# pm2013.net
KiCad netlist of a schematic drawn in EAGLE
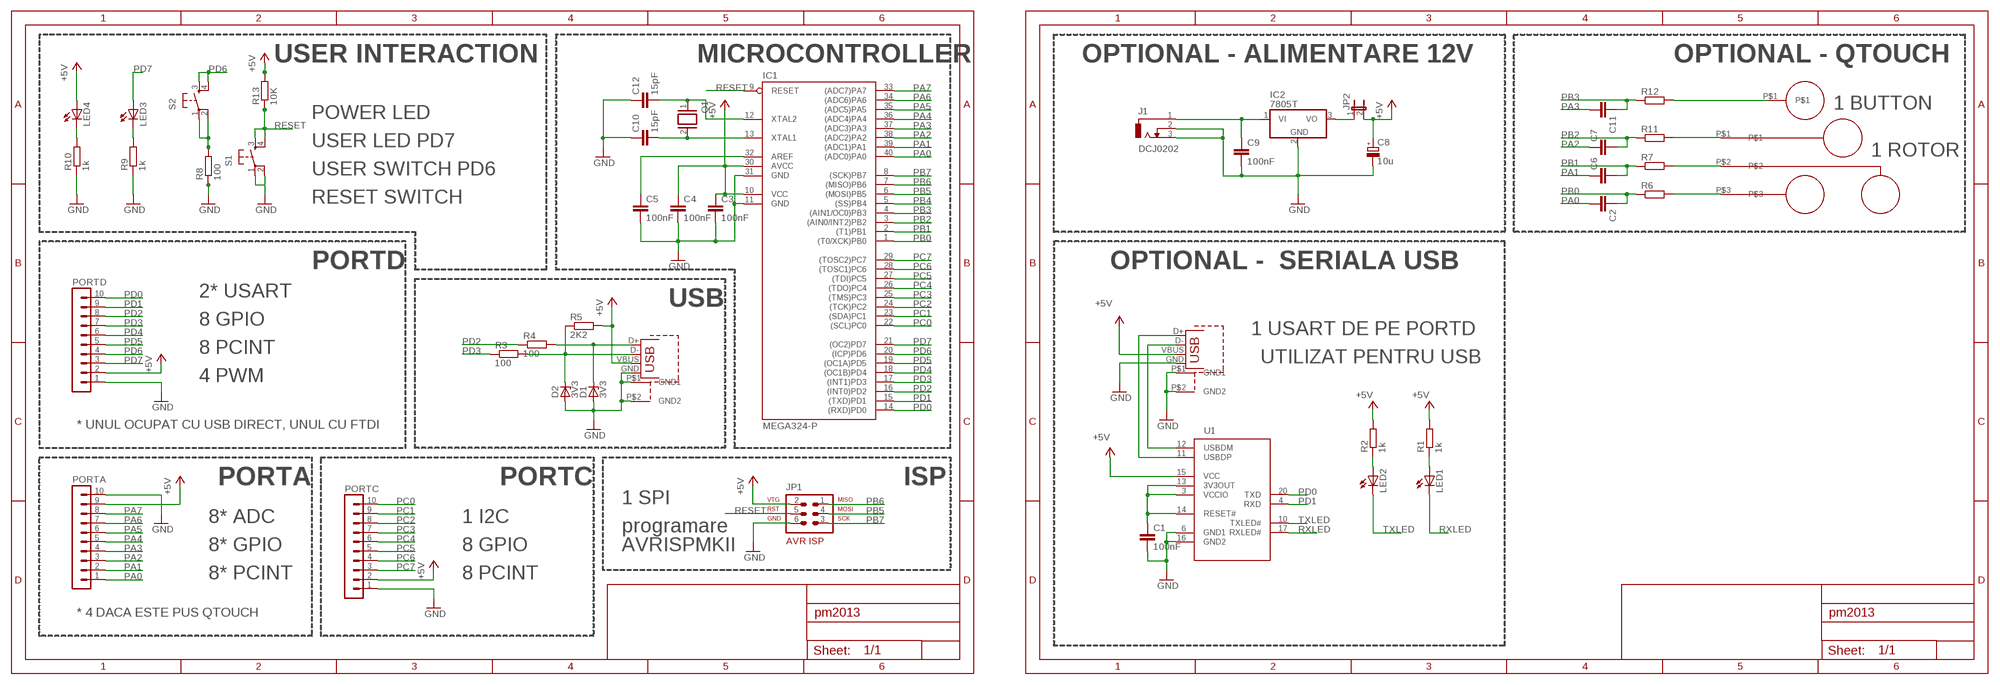
[diagram p0: schematic, sheet 1]

(export (version "E")
  (design (tool "Eeschema 10.0.6"))
  (components
    (comp (ref "C1")
      (value "100nF")
      (footprint "eagle-import:C025-025X050")
      (libsource (lib "eagle-import") (part "C-EU025-025X050"))
    )
    (comp (ref "C2")
      (value "C-EUC1206")
      (footprint "eagle-import:C1206")
      (libsource (lib "eagle-import") (part "C-EUC1206"))
    )
    (comp (ref "C3")
      (value "100nF")
      (footprint "eagle-import:C025-025X050")
      (libsource (lib "eagle-import") (part "C-EU025-025X050"))
    )
    (comp (ref "C4")
      (value "100nF")
      (footprint "eagle-import:C025-025X050")
      (libsource (lib "eagle-import") (part "C-EU025-025X050"))
    )
    (comp (ref "C5")
      (value "100nF")
      (footprint "eagle-import:C025-025X050")
      (libsource (lib "eagle-import") (part "C-EU025-025X050"))
    )
    (comp (ref "C6")
      (value "C-EUC1206")
      (footprint "eagle-import:C1206")
      (libsource (lib "eagle-import") (part "C-EUC1206"))
    )
    (comp (ref "C7")
      (value "C-EUC1206")
      (footprint "eagle-import:C1206")
      (libsource (lib "eagle-import") (part "C-EUC1206"))
    )
    (comp (ref "C8")
      (value "10u")
      (footprint "eagle-import:E2,5-5")
      (libsource (lib "eagle-import") (part "CPOL-EUE2.5-5"))
    )
    (comp (ref "C9")
      (value "100nF")
      (footprint "eagle-import:C025-025X050")
      (libsource (lib "eagle-import") (part "C-EU025-025X050"))
    )
    (comp (ref "C10")
      (value "15pF")
      (footprint "eagle-import:C025-025X050")
      (libsource (lib "eagle-import") (part "C-EU025-025X050"))
    )
    (comp (ref "C11")
      (value "C-EUC1206")
      (footprint "eagle-import:C1206")
      (libsource (lib "eagle-import") (part "C-EUC1206"))
    )
    (comp (ref "C12")
      (value "15pF")
      (footprint "eagle-import:C025-025X050")
      (libsource (lib "eagle-import") (part "C-EU025-025X050"))
    )
    (comp (ref "D1")
      (value "3V3")
      (footprint "eagle-import:DO34Z7")
      (libsource (lib "eagle-import") (part "ZENER-DIODEDO34-7"))
    )
    (comp (ref "D2")
      (value "3V3")
      (footprint "eagle-import:DO34Z7")
      (libsource (lib "eagle-import") (part "ZENER-DIODEDO34-7"))
    )
    (comp (ref "IC1")
      (value "MEGA324-P")
      (footprint "eagle-import:DIL40")
      (fields (field (name "MPN") "ATMEGA16-16PU"))
      (libsource (lib "eagle-import") (part "MEGA16-P"))
    )
    (comp (ref "IC2")
      (value "7805T")
      (footprint "eagle-import:TO220H")
      (libsource (lib "eagle-import") (part "78T05"))
    )
    (comp (ref "J1")
      (value "DCJ0202")
      (footprint "eagle-import:DCJ0202")
      (libsource (lib "eagle-import") (part "DCJ0202"))
    )
    (comp (ref "JP1")
      (value "AVR-ISP-6")
      (footprint "eagle-import:AVR-ISP-6")
      (libsource (lib "eagle-import") (part "AVR-ISP-6"))
    )
    (comp (ref "JP2")
      (value "JP1E")
      (footprint "eagle-import:JP1")
      (libsource (lib "eagle-import") (part "JP1E"))
    )
    (comp (ref "LED1")
      (value "TLLR4400")
      (footprint "eagle-import:LED3MM")
      (fields
        (field (name "MF") "VISHAY SEMICONDUCTOR")
        (field (name "MF_1") "VISHAY SEMICONDUCTOR")
        (field (name "OC_FARNELL") "1612437")
      )
      (libsource (lib "eagle-import") (part "TLLR4400"))
    )
    (comp (ref "LED2")
      (value "TLLR4400")
      (footprint "eagle-import:LED3MM")
      (fields
        (field (name "MF") "VISHAY SEMICONDUCTOR")
        (field (name "MF_1") "VISHAY SEMICONDUCTOR")
        (field (name "OC_FARNELL") "1612437")
      )
      (libsource (lib "eagle-import") (part "TLLR4400"))
    )
    (comp (ref "LED3")
      (value "TLLR4400")
      (footprint "eagle-import:LED3MM")
      (fields (field (name "MF") "VISHAY SEMICONDUCTOR"))
      (libsource (lib "eagle-import") (part "TLLR4400"))
    )
    (comp (ref "LED4")
      (value "TLLR4400")
      (footprint "eagle-import:LED3MM")
      (fields (field (name "MF") "VISHAY SEMICONDUCTOR"))
      (libsource (lib "eagle-import") (part "TLLR4400"))
    )
    (comp (ref "PORTA")
      (value "MA10-1W")
      (footprint "eagle-import:MA10-1W")
      (libsource (lib "eagle-import") (part "MA10-1W"))
    )
    (comp (ref "PORTC")
      (value "MA10-1W")
      (footprint "eagle-import:MA10-1W")
      (libsource (lib "eagle-import") (part "MA10-1W"))
    )
    (comp (ref "PORTD")
      (value "MA10-1W")
      (footprint "eagle-import:MA10-1W")
      (libsource (lib "eagle-import") (part "MA10-1W"))
    )
    (comp (ref "Q1")
      (value "XTAL/S")
      (footprint "eagle-import:QS")
      (libsource (lib "eagle-import") (part "XTAL/S"))
    )
    (comp (ref "R1")
      (value "1k")
      (footprint "eagle-import:0204_7")
      (libsource (lib "eagle-import") (part "R-EU_0204/7"))
    )
    (comp (ref "R2")
      (value "1k")
      (footprint "eagle-import:0204_7")
      (libsource (lib "eagle-import") (part "R-EU_0204/7"))
    )
    (comp (ref "R3")
      (value "100")
      (footprint "eagle-import:0204_7")
      (libsource (lib "eagle-import") (part "R-EU_0204/7"))
    )
    (comp (ref "R4")
      (value "100")
      (footprint "eagle-import:0204_7")
      (libsource (lib "eagle-import") (part "R-EU_0204/7"))
    )
    (comp (ref "R5")
      (value "2K2")
      (footprint "eagle-import:0204_7")
      (libsource (lib "eagle-import") (part "R-EU_0204/7"))
    )
    (comp (ref "R6")
      (value "R-EU_M1206")
      (footprint "eagle-import:M1206")
      (libsource (lib "eagle-import") (part "resistor_R-EU_M1206"))
    )
    (comp (ref "R7")
      (value "R-EU_M1206")
      (footprint "eagle-import:M1206")
      (libsource (lib "eagle-import") (part "resistor_R-EU_M1206"))
    )
    (comp (ref "R8")
      (value "100")
      (footprint "eagle-import:0204_7")
      (libsource (lib "eagle-import") (part "R-EU_0204/7"))
    )
    (comp (ref "R9")
      (value "1k")
      (footprint "eagle-import:0204_7")
      (libsource (lib "eagle-import") (part "resistor_R-EU_0204/7"))
    )
    (comp (ref "R10")
      (value "1k")
      (footprint "eagle-import:0204_7")
      (libsource (lib "eagle-import") (part "resistor_R-EU_0204/7"))
    )
    (comp (ref "R11")
      (value "R-EU_M1206")
      (footprint "eagle-import:M1206")
      (libsource (lib "eagle-import") (part "resistor_R-EU_M1206"))
    )
    (comp (ref "R12")
      (value "R-EU_M1206")
      (footprint "eagle-import:M1206")
      (libsource (lib "eagle-import") (part "resistor_R-EU_M1206"))
    )
    (comp (ref "R13")
      (value "10K")
      (footprint "eagle-import:0204_7")
      (libsource (lib "eagle-import") (part "R-EU_0204/7"))
    )
    (comp (ref "S1")
      (value "TAC_SWITCHPTH")
      (footprint "eagle-import:TACTILE-PTH")
      (libsource (lib "eagle-import") (part "TAC_SWITCHPTH"))
    )
    (comp (ref "S2")
      (value "TAC_SWITCHPTH")
      (footprint "eagle-import:TACTILE-PTH")
      (libsource (lib "eagle-import") (part "TAC_SWITCHPTH"))
    )
    (comp (ref "U$1")
      (value "ROTOR_ELECTRODE_TOUCH")
      (footprint "eagle-import:ROTOR_ELECTRODE_TOUCH")
      (libsource (lib "eagle-import") (part "ROTOR_ELECTRODE_TOUCH"))
    )
    (comp (ref "U$2")
      (value "SIMPLE_ELECTRODE_TOUCH")
      (footprint "eagle-import:SIMPLE_ELECTRODE_TOUCH")
      (libsource (lib "eagle-import") (part "SIMPLE_ELECTRODE_TOUCH"))
    )
    (comp (ref "U1")
      (value "FT231XS")
      (footprint "eagle-import:SSOP20")
      (libsource (lib "eagle-import") (part "FT231XS"))
    )
    (comp (ref "X1")
      (value "USB")
      (footprint "eagle-import:USB-B-PTH")
      (libsource (lib "eagle-import") (part "USB"))
    )
    (comp (ref "X2")
      (value "USBPTH")
      (footprint "eagle-import:USB-B-PTH")
      (libsource (lib "eagle-import") (part "USB"))
    )
  )
  (nets
    (net (code "1") (name "+5V") (class "Default")
      (node (ref "C3") (pin "1") (pinfunction "1_1") (pintype "passive"))
      (node (ref "C4") (pin "1") (pinfunction "1_1") (pintype "passive"))
      (node (ref "C8") (pin "+") (pinfunction "+_+") (pintype "passive"))
      (node (ref "IC1") (pin "10") (pinfunction "VCC_10") (pintype "power_in"))
      (node (ref "IC1") (pin "30") (pinfunction "AVCC_30") (pintype "power_in"))
      (node (ref "JP1") (pin "2") (pinfunction "2_2") (pintype "passive"))
      (node (ref "JP2") (pin "2") (pinfunction "2_2") (pintype "passive"))
      (node (ref "LED4") (pin "A") (pinfunction "A_A") (pintype "passive"))
      (node (ref "PORTA") (pin "9") (pinfunction "9_9") (pintype "passive"))
      (node (ref "PORTC") (pin "2") (pinfunction "2_2") (pintype "passive"))
      (node (ref "PORTD") (pin "2") (pinfunction "2_2") (pintype "passive"))
      (node (ref "R1") (pin "2") (pinfunction "2_2") (pintype "passive"))
      (node (ref "R13") (pin "2") (pinfunction "2_2") (pintype "passive"))
      (node (ref "R2") (pin "2") (pinfunction "2_2") (pintype "passive"))
      (node (ref "R5") (pin "2") (pinfunction "2_2") (pintype "passive"))
      (node (ref "U1") (pin "15") (pinfunction "VCC_15") (pintype "power_in"))
      (node (ref "X1") (pin "VBUS") (pinfunction "VBUS_VBUS") (pintype "bidirectional"))
      (node (ref "X2") (pin "VBUS") (pinfunction "VBUS_VBUS") (pintype "bidirectional"))
    )
    (net (code "2") (name "/PA0") (class "Default")
      (node (ref "C2") (pin "2") (pinfunction "2_2") (pintype "passive"))
      (node (ref "IC1") (pin "40") (pinfunction "(ADC0)PA0_40") (pintype "bidirectional"))
      (node (ref "PORTA") (pin "1") (pinfunction "1_1") (pintype "passive"))
    )
    (net (code "3") (name "/PA1") (class "Default")
      (node (ref "C6") (pin "1") (pinfunction "1_1") (pintype "passive"))
      (node (ref "IC1") (pin "39") (pinfunction "(ADC1)PA1_39") (pintype "bidirectional"))
      (node (ref "PORTA") (pin "2") (pinfunction "2_2") (pintype "passive"))
    )
    (net (code "4") (name "/PA2") (class "Default")
      (node (ref "C7") (pin "1") (pinfunction "1_1") (pintype "passive"))
      (node (ref "IC1") (pin "38") (pinfunction "(ADC2)PA2_38") (pintype "bidirectional"))
      (node (ref "PORTA") (pin "3") (pinfunction "3_3") (pintype "passive"))
    )
    (net (code "5") (name "/PA3") (class "Default")
      (node (ref "C11") (pin "2") (pinfunction "2_2") (pintype "passive"))
      (node (ref "IC1") (pin "37") (pinfunction "(ADC3)PA3_37") (pintype "bidirectional"))
      (node (ref "PORTA") (pin "4") (pinfunction "4_4") (pintype "passive"))
    )
    (net (code "6") (name "/PA4") (class "Default")
      (node (ref "IC1") (pin "36") (pinfunction "(ADC4)PA4_36") (pintype "bidirectional"))
      (node (ref "PORTA") (pin "5") (pinfunction "5_5") (pintype "passive"))
    )
    (net (code "7") (name "/PA5") (class "Default")
      (node (ref "IC1") (pin "35") (pinfunction "(ADC5)PA5_35") (pintype "bidirectional"))
      (node (ref "PORTA") (pin "6") (pinfunction "6_6") (pintype "passive"))
    )
    (net (code "8") (name "/PA6") (class "Default")
      (node (ref "IC1") (pin "34") (pinfunction "(ADC6)PA6_34") (pintype "bidirectional"))
      (node (ref "PORTA") (pin "7") (pinfunction "7_7") (pintype "passive"))
    )
    (net (code "9") (name "/PA7") (class "Default")
      (node (ref "IC1") (pin "33") (pinfunction "(ADC7)PA7_33") (pintype "bidirectional"))
      (node (ref "PORTA") (pin "8") (pinfunction "8_8") (pintype "passive"))
    )
    (net (code "10") (name "/PB0") (class "Default")
      (node (ref "C2") (pin "1") (pinfunction "1_1") (pintype "passive"))
      (node (ref "IC1") (pin "1") (pinfunction "(T0/XCK)PB0_1") (pintype "bidirectional"))
      (node (ref "R6") (pin "1") (pinfunction "1_1") (pintype "passive"))
    )
    (net (code "11") (name "/PB1") (class "Default")
      (node (ref "C6") (pin "2") (pinfunction "2_2") (pintype "passive"))
      (node (ref "IC1") (pin "2") (pinfunction "(T1)PB1_2") (pintype "bidirectional"))
      (node (ref "R7") (pin "1") (pinfunction "1_1") (pintype "passive"))
    )
    (net (code "12") (name "/PB2") (class "Default")
      (node (ref "C7") (pin "2") (pinfunction "2_2") (pintype "passive"))
      (node (ref "IC1") (pin "3") (pinfunction "(AIN0/INT2)PB2_3") (pintype "bidirectional"))
      (node (ref "R11") (pin "1") (pinfunction "1_1") (pintype "passive"))
    )
    (net (code "13") (name "/PB3") (class "Default")
      (node (ref "C11") (pin "1") (pinfunction "1_1") (pintype "passive"))
      (node (ref "IC1") (pin "4") (pinfunction "(AIN1/OC0)PB3_4") (pintype "bidirectional"))
      (node (ref "R12") (pin "1") (pinfunction "1_1") (pintype "passive"))
    )
    (net (code "14") (name "/PB4") (class "Default")
      (node (ref "IC1") (pin "5") (pinfunction "(SS)PB4_5") (pintype "bidirectional"))
    )
    (net (code "15") (name "/PB5") (class "Default")
      (node (ref "IC1") (pin "6") (pinfunction "(MOSI)PB5_6") (pintype "bidirectional"))
      (node (ref "JP1") (pin "4") (pinfunction "4_4") (pintype "passive"))
    )
    (net (code "16") (name "/PB6") (class "Default")
      (node (ref "IC1") (pin "7") (pinfunction "(MISO)PB6_7") (pintype "bidirectional"))
      (node (ref "JP1") (pin "1") (pinfunction "1_1") (pintype "passive"))
    )
    (net (code "17") (name "/PB7") (class "Default")
      (node (ref "IC1") (pin "8") (pinfunction "(SCK)PB7_8") (pintype "bidirectional"))
      (node (ref "JP1") (pin "3") (pinfunction "3_3") (pintype "passive"))
    )
    (net (code "18") (name "/PC0") (class "Default")
      (node (ref "IC1") (pin "22") (pinfunction "(SCL)PC0_22") (pintype "bidirectional"))
      (node (ref "PORTC") (pin "10") (pinfunction "10_10") (pintype "passive"))
    )
    (net (code "19") (name "/PC1") (class "Default")
      (node (ref "IC1") (pin "23") (pinfunction "(SDA)PC1_23") (pintype "bidirectional"))
      (node (ref "PORTC") (pin "9") (pinfunction "9_9") (pintype "passive"))
    )
    (net (code "20") (name "/PC2") (class "Default")
      (node (ref "IC1") (pin "24") (pinfunction "(TCK)PC2_24") (pintype "bidirectional"))
      (node (ref "PORTC") (pin "8") (pinfunction "8_8") (pintype "passive"))
    )
    (net (code "21") (name "/PC3") (class "Default")
      (node (ref "IC1") (pin "25") (pinfunction "(TMS)PC3_25") (pintype "bidirectional"))
      (node (ref "PORTC") (pin "7") (pinfunction "7_7") (pintype "passive"))
    )
    (net (code "22") (name "/PC4") (class "Default")
      (node (ref "IC1") (pin "26") (pinfunction "(TDO)PC4_26") (pintype "bidirectional"))
      (node (ref "PORTC") (pin "6") (pinfunction "6_6") (pintype "passive"))
    )
    (net (code "23") (name "/PC5") (class "Default")
      (node (ref "IC1") (pin "27") (pinfunction "(TDI)PC5_27") (pintype "bidirectional"))
      (node (ref "PORTC") (pin "5") (pinfunction "5_5") (pintype "passive"))
    )
    (net (code "24") (name "/PC6") (class "Default")
      (node (ref "IC1") (pin "28") (pinfunction "(TOSC1)PC6_28") (pintype "bidirectional"))
      (node (ref "PORTC") (pin "4") (pinfunction "4_4") (pintype "passive"))
    )
    (net (code "25") (name "/PC7") (class "Default")
      (node (ref "IC1") (pin "29") (pinfunction "(TOSC2)PC7_29") (pintype "bidirectional"))
      (node (ref "PORTC") (pin "3") (pinfunction "3_3") (pintype "passive"))
    )
    (net (code "26") (name "/PD0") (class "Default")
      (node (ref "IC1") (pin "14") (pinfunction "(RXD)PD0_14") (pintype "bidirectional"))
      (node (ref "PORTD") (pin "10") (pinfunction "10_10") (pintype "passive"))
      (node (ref "U1") (pin "20") (pinfunction "TXD_20") (pintype "output"))
    )
    (net (code "27") (name "/PD1") (class "Default")
      (node (ref "IC1") (pin "15") (pinfunction "(TXD)PD1_15") (pintype "bidirectional"))
      (node (ref "PORTD") (pin "9") (pinfunction "9_9") (pintype "passive"))
      (node (ref "U1") (pin "4") (pinfunction "RXD_4") (pintype "input"))
    )
    (net (code "28") (name "/PD2") (class "Default")
      (node (ref "IC1") (pin "16") (pinfunction "(INT0)PD2_16") (pintype "bidirectional"))
      (node (ref "PORTD") (pin "8") (pinfunction "8_8") (pintype "passive"))
      (node (ref "R4") (pin "1") (pinfunction "1_1") (pintype "passive"))
    )
    (net (code "29") (name "/PD3") (class "Default")
      (node (ref "IC1") (pin "17") (pinfunction "(INT1)PD3_17") (pintype "bidirectional"))
      (node (ref "PORTD") (pin "7") (pinfunction "7_7") (pintype "passive"))
      (node (ref "R3") (pin "1") (pinfunction "1_1") (pintype "passive"))
    )
    (net (code "30") (name "/PD4") (class "Default")
      (node (ref "IC1") (pin "18") (pinfunction "(OC1B)PD4_18") (pintype "bidirectional"))
      (node (ref "PORTD") (pin "6") (pinfunction "6_6") (pintype "passive"))
    )
    (net (code "31") (name "/PD5") (class "Default")
      (node (ref "IC1") (pin "19") (pinfunction "(OC1A)PD5_19") (pintype "bidirectional"))
      (node (ref "PORTD") (pin "5") (pinfunction "5_5") (pintype "passive"))
    )
    (net (code "32") (name "/PD6") (class "Default")
      (node (ref "IC1") (pin "20") (pinfunction "(ICP)PD6_20") (pintype "bidirectional"))
      (node (ref "PORTD") (pin "4") (pinfunction "4_4") (pintype "passive"))
      (node (ref "S2") (pin "3") (pinfunction "3_3") (pintype "passive"))
      (node (ref "S2") (pin "4") (pinfunction "4_4") (pintype "passive"))
    )
    (net (code "33") (name "/PD7") (class "Default")
      (node (ref "IC1") (pin "21") (pinfunction "(OC2)PD7_21") (pintype "bidirectional"))
      (node (ref "LED3") (pin "A") (pinfunction "A_A") (pintype "passive"))
      (node (ref "PORTD") (pin "3") (pinfunction "3_3") (pintype "passive"))
    )
    (net (code "34") (name "/RESET") (class "Default")
      (node (ref "IC1") (pin "9") (pinfunction "RESET_9") (pintype "input"))
      (node (ref "JP1") (pin "5") (pinfunction "5_5") (pintype "passive"))
      (node (ref "R13") (pin "1") (pinfunction "1_1") (pintype "passive"))
      (node (ref "S1") (pin "3") (pinfunction "3_3") (pintype "passive"))
      (node (ref "S1") (pin "4") (pinfunction "4_4") (pintype "passive"))
    )
    (net (code "35") (name "/RXLED") (class "Default")
      (node (ref "LED1") (pin "K") (pinfunction "C_K") (pintype "passive"))
      (node (ref "U1") (pin "17") (pinfunction "RXLED#_17") (pintype "output"))
    )
    (net (code "36") (name "/TXLED") (class "Default")
      (node (ref "LED2") (pin "K") (pinfunction "C_K") (pintype "passive"))
      (node (ref "U1") (pin "10") (pinfunction "TXLED#_10") (pintype "output"))
    )
    (net (code "37") (name "GND") (class "Default")
      (node (ref "C1") (pin "2") (pinfunction "2_2") (pintype "passive"))
      (node (ref "C10") (pin "1") (pinfunction "1_1") (pintype "passive"))
      (node (ref "C12") (pin "1") (pinfunction "1_1") (pintype "passive"))
      (node (ref "C3") (pin "2") (pinfunction "2_2") (pintype "passive"))
      (node (ref "C4") (pin "2") (pinfunction "2_2") (pintype "passive"))
      (node (ref "C5") (pin "2") (pinfunction "2_2") (pintype "passive"))
      (node (ref "C8") (pin "-") (pinfunction "-_-") (pintype "passive"))
      (node (ref "C9") (pin "2") (pinfunction "2_2") (pintype "passive"))
      (node (ref "D1") (pin "A") (pinfunction "A_A") (pintype "passive"))
      (node (ref "D2") (pin "A") (pinfunction "A_A") (pintype "passive"))
      (node (ref "IC1") (pin "11") (pinfunction "GND_11") (pintype "power_in"))
      (node (ref "IC1") (pin "31") (pinfunction "GND_31") (pintype "power_in"))
      (node (ref "IC2") (pin "2") (pinfunction "GND_2") (pintype "passive"))
      (node (ref "J1") (pin "2") (pinfunction "2_2") (pintype "passive"))
      (node (ref "J1") (pin "3") (pinfunction "3_3") (pintype "passive"))
      (node (ref "JP1") (pin "6") (pinfunction "6_6") (pintype "passive"))
      (node (ref "PORTA") (pin "10") (pinfunction "10_10") (pintype "passive"))
      (node (ref "PORTC") (pin "1") (pinfunction "1_1") (pintype "passive"))
      (node (ref "PORTD") (pin "1") (pinfunction "1_1") (pintype "passive"))
      (node (ref "R10") (pin "1") (pinfunction "1_1") (pintype "passive"))
      (node (ref "R8") (pin "1") (pinfunction "1_1") (pintype "passive"))
      (node (ref "R9") (pin "1") (pinfunction "1_1") (pintype "passive"))
      (node (ref "S1") (pin "1") (pinfunction "1_1") (pintype "passive"))
      (node (ref "S1") (pin "2") (pinfunction "2_2") (pintype "passive"))
      (node (ref "U1") (pin "16") (pinfunction "GND2_16") (pintype "power_in"))
      (node (ref "U1") (pin "6") (pinfunction "GND1_6") (pintype "power_in"))
      (node (ref "X1") (pin "GND") (pinfunction "GND_GND") (pintype "bidirectional"))
      (node (ref "X1") (pin "P$1") (pinfunction "GND1_P$1") (pintype "bidirectional"))
      (node (ref "X1") (pin "P$2") (pinfunction "GND2_P$2") (pintype "bidirectional"))
      (node (ref "X2") (pin "GND") (pinfunction "GND_GND") (pintype "bidirectional"))
      (node (ref "X2") (pin "P$1") (pinfunction "GND1_P$1") (pintype "bidirectional"))
      (node (ref "X2") (pin "P$2") (pinfunction "GND2_P$2") (pintype "bidirectional"))
    )
    (net (code "38") (name "Net-(D1-PadC)") (class "Default")
      (node (ref "D1") (pin "C") (pinfunction "C_C") (pintype "passive"))
      (node (ref "R4") (pin "2") (pinfunction "2_2") (pintype "passive"))
      (node (ref "X2") (pin "D+") (pinfunction "D+_D+") (pintype "bidirectional"))
    )
    (net (code "39") (name "Net-(D2-PadC)") (class "Default")
      (node (ref "D2") (pin "C") (pinfunction "C_C") (pintype "passive"))
      (node (ref "R3") (pin "2") (pinfunction "2_2") (pintype "passive"))
      (node (ref "R5") (pin "1") (pinfunction "1_1") (pintype "passive"))
      (node (ref "X2") (pin "D-") (pinfunction "D-_D-") (pintype "bidirectional"))
    )
    (net (code "40") (name "Net-(IC1-AREF)") (class "Default")
      (node (ref "C5") (pin "1") (pinfunction "1_1") (pintype "passive"))
      (node (ref "IC1") (pin "32") (pinfunction "AREF_32") (pintype "passive"))
    )
    (net (code "41") (name "Net-(IC1-XTAL1)") (class "Default")
      (node (ref "C10") (pin "2") (pinfunction "2_2") (pintype "passive"))
      (node (ref "IC1") (pin "13") (pinfunction "XTAL1_13") (pintype "bidirectional"))
      (node (ref "Q1") (pin "2") (pinfunction "2_2") (pintype "passive"))
    )
    (net (code "42") (name "Net-(IC1-XTAL2)") (class "Default")
      (node (ref "C12") (pin "2") (pinfunction "2_2") (pintype "passive"))
      (node (ref "IC1") (pin "12") (pinfunction "XTAL2_12") (pintype "bidirectional"))
      (node (ref "Q1") (pin "1") (pinfunction "1_1") (pintype "passive"))
    )
    (net (code "43") (name "Net-(IC2-VI)") (class "Default")
      (node (ref "C9") (pin "1") (pinfunction "1_1") (pintype "passive"))
      (node (ref "IC2") (pin "1") (pinfunction "VI_1") (pintype "input"))
      (node (ref "J1") (pin "1") (pinfunction "1_1") (pintype "passive"))
    )
    (net (code "44") (name "Net-(IC2-VO)") (class "Default")
      (node (ref "IC2") (pin "3") (pinfunction "VO_3") (pintype "passive"))
      (node (ref "JP2") (pin "1") (pinfunction "1_1") (pintype "passive"))
    )
    (net (code "45") (name "Net-(LED1-PadA)") (class "Default")
      (node (ref "LED1") (pin "A") (pinfunction "A_A") (pintype "passive"))
      (node (ref "R1") (pin "1") (pinfunction "1_1") (pintype "passive"))
    )
    (net (code "46") (name "Net-(LED2-PadA)") (class "Default")
      (node (ref "LED2") (pin "A") (pinfunction "A_A") (pintype "passive"))
      (node (ref "R2") (pin "1") (pinfunction "1_1") (pintype "passive"))
    )
    (net (code "47") (name "Net-(LED3-C)") (class "Default")
      (node (ref "LED3") (pin "K") (pinfunction "C_K") (pintype "passive"))
      (node (ref "R9") (pin "2") (pinfunction "2_2") (pintype "passive"))
    )
    (net (code "48") (name "Net-(LED4-C)") (class "Default")
      (node (ref "LED4") (pin "K") (pinfunction "C_K") (pintype "passive"))
      (node (ref "R10") (pin "2") (pinfunction "2_2") (pintype "passive"))
    )
    (net (code "49") (name "Net-(R6-Pad2)") (class "Default")
      (node (ref "R6") (pin "2") (pinfunction "2_2") (pintype "passive"))
      (node (ref "U$1") (pin "P$3") (pinfunction "P$3_P$3") (pintype "bidirectional"))
    )
    (net (code "50") (name "Net-(R7-Pad2)") (class "Default")
      (node (ref "R7") (pin "2") (pinfunction "2_2") (pintype "passive"))
      (node (ref "U$1") (pin "P$2") (pinfunction "P$2_P$2") (pintype "bidirectional"))
    )
    (net (code "51") (name "Net-(R8-Pad2)") (class "Default")
      (node (ref "R8") (pin "2") (pinfunction "2_2") (pintype "passive"))
      (node (ref "S2") (pin "1") (pinfunction "1_1") (pintype "passive"))
      (node (ref "S2") (pin "2") (pinfunction "2_2") (pintype "passive"))
    )
    (net (code "52") (name "Net-(R11-Pad2)") (class "Default")
      (node (ref "R11") (pin "2") (pinfunction "2_2") (pintype "passive"))
      (node (ref "U$1") (pin "P$1") (pinfunction "P$1_P$1") (pintype "bidirectional"))
    )
    (net (code "53") (name "Net-(R12-Pad2)") (class "Default")
      (node (ref "R12") (pin "2") (pinfunction "2_2") (pintype "passive"))
      (node (ref "U$2") (pin "P$1") (pinfunction "P$1_P$1") (pintype "bidirectional"))
    )
    (net (code "54") (name "Net-(U1-3V3OUT)") (class "Default")
      (node (ref "C1") (pin "1") (pinfunction "1_1") (pintype "passive"))
      (node (ref "U1") (pin "13") (pinfunction "3V3OUT_13") (pintype "output"))
      (node (ref "U1") (pin "14") (pinfunction "RESET#_14") (pintype "input"))
      (node (ref "U1") (pin "3") (pinfunction "VCCIO_3") (pintype "power_in"))
    )
    (net (code "55") (name "Net-(U1-USBDM)") (class "Default")
      (node (ref "U1") (pin "12") (pinfunction "USBDM_12") (pintype "bidirectional"))
      (node (ref "X1") (pin "D-") (pinfunction "D-_D-") (pintype "bidirectional"))
    )
    (net (code "56") (name "Net-(U1-USBDP)") (class "Default")
      (node (ref "U1") (pin "11") (pinfunction "USBDP_11") (pintype "bidirectional"))
      (node (ref "X1") (pin "D+") (pinfunction "D+_D+") (pintype "bidirectional"))
    )
  )
)
